# power.net
KiCad netlist of a schematic drawn in Altium Designer
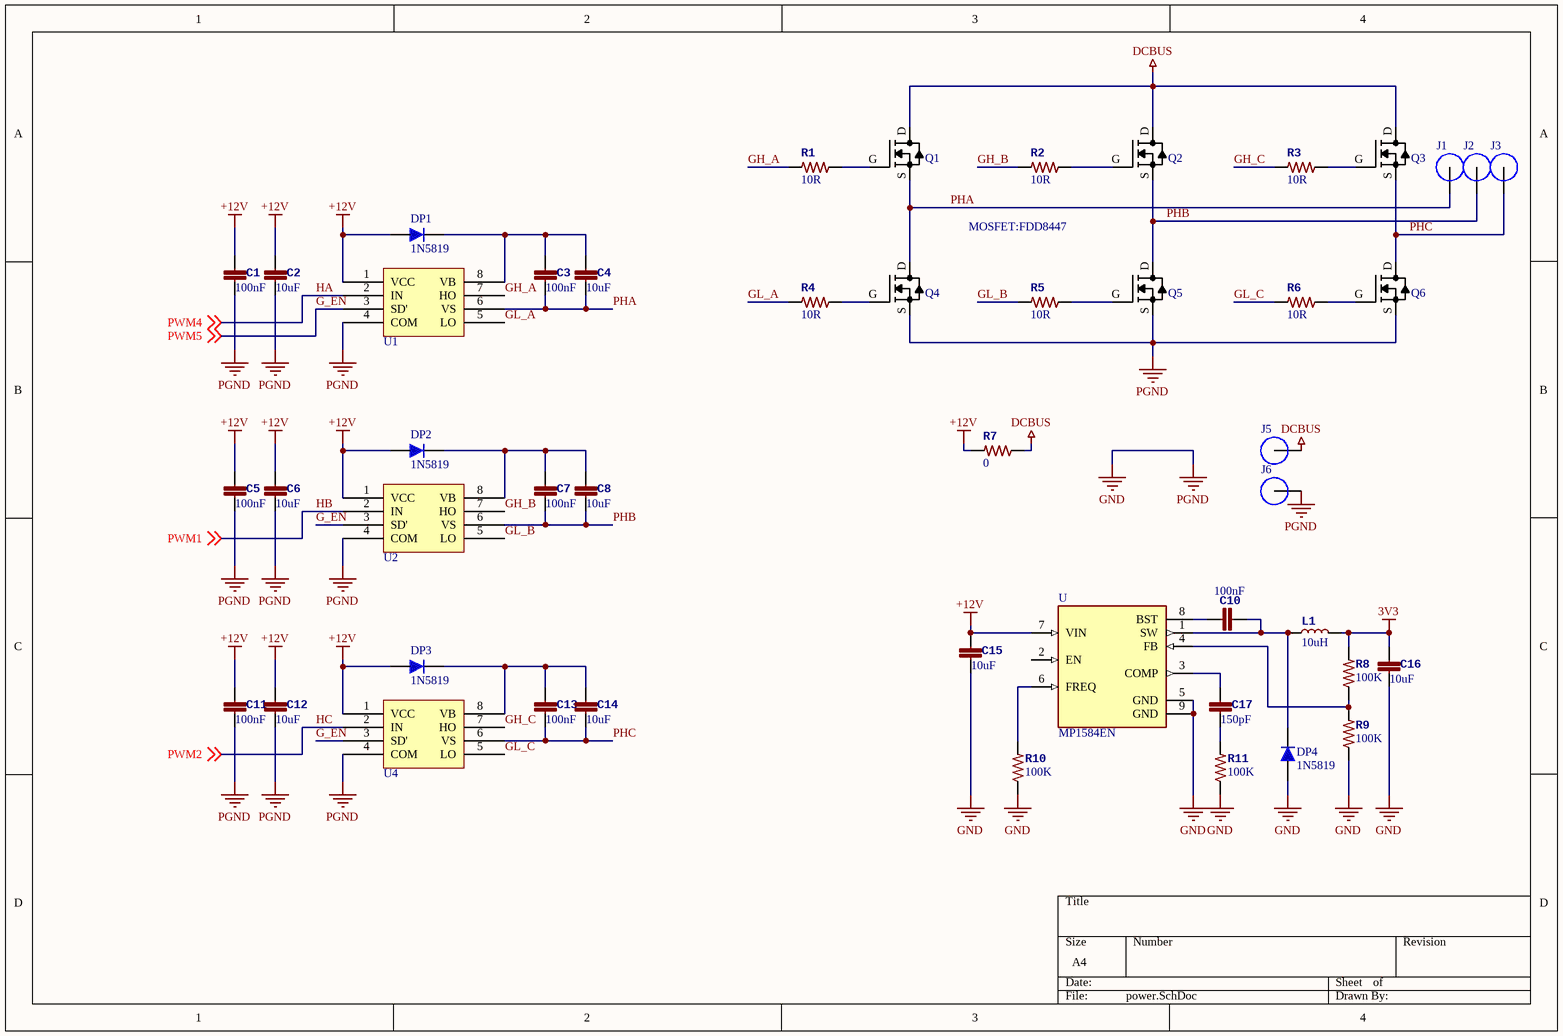
[diagram p0: power.SchDoc]

(export (version "E")
  (design (tool "Eeschema 10.0.6"))
  (components
    (comp (ref "C1")
      (value "100nF")
      (footprint "_1206")
      (fields (field (name "Comment") "Cap"))
      (libsource (lib "") (part "Cap_1_1"))
    )
    (comp (ref "C2")
      (value "10uF")
      (footprint "_1206")
      (fields (field (name "Comment") "Cap"))
      (libsource (lib "") (part "Cap_1_1"))
    )
    (comp (ref "C3")
      (value "100nF")
      (footprint "_1206")
      (fields (field (name "Comment") "Cap"))
      (libsource (lib "") (part "Cap_1_1"))
    )
    (comp (ref "C4")
      (value "10uF")
      (footprint "_1206")
      (fields (field (name "Comment") "Cap"))
      (libsource (lib "") (part "Cap_1_1"))
    )
    (comp (ref "C5")
      (value "100nF")
      (footprint "_1206")
      (fields (field (name "Comment") "Cap"))
      (libsource (lib "") (part "Cap_1_1"))
    )
    (comp (ref "C6")
      (value "10uF")
      (footprint "_1206")
      (fields (field (name "Comment") "Cap"))
      (libsource (lib "") (part "Cap_1_1"))
    )
    (comp (ref "C7")
      (value "100nF")
      (footprint "_1206")
      (fields (field (name "Comment") "Cap"))
      (libsource (lib "") (part "Cap_1_1"))
    )
    (comp (ref "C8")
      (value "10uF")
      (footprint "_1206")
      (fields (field (name "Comment") "Cap"))
      (libsource (lib "") (part "Cap_1_1"))
    )
    (comp (ref "C10")
      (value "100nF")
      (footprint "_0805")
      (fields (field (name "Comment") "Cap"))
      (libsource (lib "Passives_Integrated_Library") (part "Cap_1"))
    )
    (comp (ref "C11")
      (value "100nF")
      (footprint "_1206")
      (fields (field (name "Comment") "Cap"))
      (libsource (lib "") (part "Cap_1_1"))
    )
    (comp (ref "C12")
      (value "10uF")
      (footprint "_1206")
      (fields (field (name "Comment") "Cap"))
      (libsource (lib "") (part "Cap_1_1"))
    )
    (comp (ref "C13")
      (value "100nF")
      (footprint "_1206")
      (fields (field (name "Comment") "Cap"))
      (libsource (lib "") (part "Cap_1_1"))
    )
    (comp (ref "C14")
      (value "10uF")
      (footprint "_1206")
      (fields (field (name "Comment") "Cap"))
      (libsource (lib "") (part "Cap_1_1"))
    )
    (comp (ref "C15")
      (value "10uF")
      (footprint "_1206")
      (fields (field (name "Comment") "Cap"))
      (libsource (lib "") (part "Cap_1_1"))
    )
    (comp (ref "C16")
      (value "10uF")
      (footprint "_1206")
      (fields (field (name "Comment") "Cap"))
      (libsource (lib "") (part "Cap_1_1"))
    )
    (comp (ref "C17")
      (value "150pF")
      (footprint "_0805")
      (fields (field (name "Comment") "Cap"))
      (libsource (lib "") (part "Cap_1_1"))
    )
    (comp (ref "DP1")
      (value "1N5819")
      (footprint "430X270D")
      (description "Schottkey Rectifiers")
      (fields (field (name "DESIGNER") "Abbas Basereh"))
      (libsource (lib "Diodes_Integrated_Library") (part "1N5819"))
    )
    (comp (ref "DP2")
      (value "1N5819")
      (footprint "430X270D")
      (description "Schottkey Rectifiers")
      (fields (field (name "DESIGNER") "Abbas Basereh"))
      (libsource (lib "Diodes_Integrated_Library") (part "1N5819"))
    )
    (comp (ref "DP3")
      (value "1N5819")
      (footprint "430X270D")
      (description "Schottkey Rectifiers")
      (fields (field (name "DESIGNER") "Abbas Basereh"))
      (libsource (lib "Diodes_Integrated_Library") (part "1N5819"))
    )
    (comp (ref "DP4")
      (value "1N5819")
      (footprint "430X270D")
      (description "Schottkey Rectifiers")
      (fields (field (name "DESIGNER") "Abbas Basereh"))
      (libsource (lib "Diodes_Integrated_Library") (part "1N5819"))
    )
    (comp (ref "J1")
      (value "~")
      (footprint "M3 Spade Hole")
      (description "M3 Spade Terminal")
      (libsource (lib "CustomComponents") (part "M3 Spade Terminal"))
    )
    (comp (ref "J2")
      (value "~")
      (footprint "M3 Spade Hole")
      (description "M3 Spade Terminal")
      (libsource (lib "CustomComponents") (part "M3 Spade Terminal"))
    )
    (comp (ref "J3")
      (value "~")
      (footprint "M3 Spade Hole")
      (description "M3 Spade Terminal")
      (libsource (lib "CustomComponents") (part "M3 Spade Terminal"))
    )
    (comp (ref "J5")
      (value "~")
      (footprint "M3 Spade Hole")
      (description "M3 Spade Terminal")
      (libsource (lib "CustomComponents") (part "M3 Spade Terminal"))
    )
    (comp (ref "J6")
      (value "~")
      (footprint "M3 Spade Hole")
      (description "M3 Spade Terminal")
      (libsource (lib "CustomComponents") (part "M3 Spade Terminal"))
    )
    (comp (ref "L1")
      (value "10uH")
      (footprint "_INDUCTOR-SMD-6.0mm")
      (fields (field (name "Comment") "Inductor"))
      (libsource (lib "Passives_Integrated_Library") (part "Inductor"))
    )
    (comp (ref "Q1")
      (value "FILL_FOOTPRINT")
      (footprint "TO229P994X240-3N")
      (description "MOSFET N-CH 30V 13A SO8FL")
      (fields
        (field (name "MANUFACTURER") "ON Semiconductor")
        (field (name "MANUFACTURER PART NUMBER") "NTMFS4935NT1G")
      )
      (libsource (lib "Integrated_Library1") (part "NTMFS4935NT1G"))
    )
    (comp (ref "Q2")
      (value "FILL_FOOTPRINT")
      (footprint "TO229P994X240-3N")
      (description "MOSFET N-CH 30V 13A SO8FL")
      (fields
        (field (name "MANUFACTURER") "ON Semiconductor")
        (field (name "MANUFACTURER PART NUMBER") "NTMFS4935NT1G")
      )
      (libsource (lib "Integrated_Library1") (part "NTMFS4935NT1G"))
    )
    (comp (ref "Q3")
      (value "FILL_FOOTPRINT")
      (footprint "TO229P994X240-3N")
      (description "MOSFET N-CH 30V 13A SO8FL")
      (fields
        (field (name "MANUFACTURER") "ON Semiconductor")
        (field (name "MANUFACTURER PART NUMBER") "NTMFS4935NT1G")
      )
      (libsource (lib "Integrated_Library1") (part "NTMFS4935NT1G"))
    )
    (comp (ref "Q4")
      (value "FILL_FOOTPRINT")
      (footprint "TO229P994X240-3N")
      (description "MOSFET N-CH 30V 13A SO8FL")
      (fields
        (field (name "MANUFACTURER") "ON Semiconductor")
        (field (name "MANUFACTURER PART NUMBER") "NTMFS4935NT1G")
      )
      (libsource (lib "Integrated_Library1") (part "NTMFS4935NT1G"))
    )
    (comp (ref "Q5")
      (value "FILL_FOOTPRINT")
      (footprint "TO229P994X240-3N")
      (description "MOSFET N-CH 30V 13A SO8FL")
      (fields
        (field (name "MANUFACTURER") "ON Semiconductor")
        (field (name "MANUFACTURER PART NUMBER") "NTMFS4935NT1G")
      )
      (libsource (lib "Integrated_Library1") (part "NTMFS4935NT1G"))
    )
    (comp (ref "Q6")
      (value "FILL_FOOTPRINT")
      (footprint "TO229P994X240-3N")
      (description "MOSFET N-CH 30V 13A SO8FL")
      (fields
        (field (name "MANUFACTURER") "ON Semiconductor")
        (field (name "MANUFACTURER PART NUMBER") "NTMFS4935NT1G")
      )
      (libsource (lib "Integrated_Library1") (part "NTMFS4935NT1G"))
    )
    (comp (ref "R1")
      (value "10R")
      (footprint "_0805")
      (fields (field (name "Comment") "Resistor"))
      (libsource (lib "Passives_Integrated_Library") (part "Resistor"))
    )
    (comp (ref "R2")
      (value "10R")
      (footprint "_0805")
      (fields (field (name "Comment") "Resistor"))
      (libsource (lib "Passives_Integrated_Library") (part "Resistor"))
    )
    (comp (ref "R3")
      (value "10R")
      (footprint "_0805")
      (fields (field (name "Comment") "Resistor"))
      (libsource (lib "Passives_Integrated_Library") (part "Resistor"))
    )
    (comp (ref "R4")
      (value "10R")
      (footprint "_0805")
      (fields (field (name "Comment") "Resistor"))
      (libsource (lib "Passives_Integrated_Library") (part "Resistor"))
    )
    (comp (ref "R5")
      (value "10R")
      (footprint "_0805")
      (fields (field (name "Comment") "Resistor"))
      (libsource (lib "Passives_Integrated_Library") (part "Resistor"))
    )
    (comp (ref "R6")
      (value "10R")
      (footprint "_0805")
      (fields (field (name "Comment") "Resistor"))
      (libsource (lib "Passives_Integrated_Library") (part "Resistor"))
    )
    (comp (ref "R7")
      (value "0")
      (footprint "_1206")
      (fields (field (name "Comment") "Resistor"))
      (libsource (lib "Passives_Integrated_Library") (part "Resistor"))
    )
    (comp (ref "R8")
      (value "100K")
      (footprint "_0805")
      (fields (field (name "Comment") "Resistor"))
      (libsource (lib "Passives_Integrated_Library") (part "Resistor"))
    )
    (comp (ref "R9")
      (value "100K")
      (footprint "_0805")
      (fields (field (name "Comment") "Resistor"))
      (libsource (lib "Passives_Integrated_Library") (part "Resistor"))
    )
    (comp (ref "R10")
      (value "100K")
      (footprint "_0805")
      (fields (field (name "Comment") "Resistor"))
      (libsource (lib "Passives_Integrated_Library") (part "Resistor"))
    )
    (comp (ref "R11")
      (value "100K")
      (footprint "_0805")
      (fields (field (name "Comment") "Resistor"))
      (libsource (lib "Passives_Integrated_Library") (part "Resistor"))
    )
    (comp (ref "U")
      (value "MP1584EN")
      (footprint "SOIC127P600X170-9N")
      (fields (field (name "MF") "Monolithic Power"))
      (libsource (lib "MP1584EN") (part "MP1584EN"))
    )
    (comp (ref "U1")
      (value "IR2104")
      (footprint "_SO08")
      (libsource (lib "Power_Electronics_Integrated_Library") (part "IR2104"))
    )
    (comp (ref "U2")
      (value "IR2104")
      (footprint "_SO08")
      (libsource (lib "Power_Electronics_Integrated_Library") (part "IR2104"))
    )
    (comp (ref "U4")
      (value "IR2104")
      (footprint "_SO08")
      (libsource (lib "Power_Electronics_Integrated_Library") (part "IR2104"))
    )
  )
  (nets
    (net (code "1") (name "+12V") (class "Default")
      (node (ref "C1") (pin "1") (pinfunction "1_1") (pintype "passive"))
      (node (ref "C11") (pin "1") (pinfunction "1_1") (pintype "passive"))
      (node (ref "C12") (pin "1") (pinfunction "1_1") (pintype "passive"))
      (node (ref "C15") (pin "1") (pinfunction "1_1") (pintype "passive"))
      (node (ref "C2") (pin "1") (pinfunction "1_1") (pintype "passive"))
      (node (ref "C5") (pin "1") (pinfunction "1_1") (pintype "passive"))
      (node (ref "C6") (pin "1") (pinfunction "1_1") (pintype "passive"))
      (node (ref "DP1") (pin "1") (pintype "passive"))
      (node (ref "DP2") (pin "1") (pintype "passive"))
      (node (ref "DP3") (pin "1") (pintype "passive"))
      (node (ref "R7") (pin "2") (pinfunction "2_2") (pintype "passive"))
      (node (ref "U") (pin "7") (pinfunction "VIN_7") (pintype "input"))
      (node (ref "U1") (pin "1") (pinfunction "VCC_1") (pintype "passive"))
      (node (ref "U2") (pin "1") (pinfunction "VCC_1") (pintype "passive"))
      (node (ref "U4") (pin "1") (pinfunction "VCC_1") (pintype "passive"))
    )
    (net (code "2") (name "/GH_A") (class "Default")
      (node (ref "R1") (pin "2") (pinfunction "2_2") (pintype "passive"))
      (node (ref "U1") (pin "7") (pinfunction "HO_7") (pintype "passive"))
    )
    (net (code "3") (name "/GH_B") (class "Default")
      (node (ref "R2") (pin "2") (pinfunction "2_2") (pintype "passive"))
      (node (ref "U2") (pin "7") (pinfunction "HO_7") (pintype "passive"))
    )
    (net (code "4") (name "/GH_C") (class "Default")
      (node (ref "R3") (pin "2") (pinfunction "2_2") (pintype "passive"))
      (node (ref "U4") (pin "7") (pinfunction "HO_7") (pintype "passive"))
    )
    (net (code "5") (name "/GL_A") (class "Default")
      (node (ref "R4") (pin "2") (pinfunction "2_2") (pintype "passive"))
      (node (ref "U1") (pin "5") (pinfunction "LO_5") (pintype "passive"))
    )
    (net (code "6") (name "/GL_B") (class "Default")
      (node (ref "R5") (pin "2") (pinfunction "2_2") (pintype "passive"))
      (node (ref "U2") (pin "5") (pinfunction "LO_5") (pintype "passive"))
    )
    (net (code "7") (name "/GL_C") (class "Default")
      (node (ref "R6") (pin "2") (pinfunction "2_2") (pintype "passive"))
      (node (ref "U4") (pin "5") (pinfunction "LO_5") (pintype "passive"))
    )
    (net (code "8") (name "/PHA") (class "Default")
      (node (ref "C3") (pin "2") (pinfunction "2_2") (pintype "passive"))
      (node (ref "C4") (pin "2") (pinfunction "2_2") (pintype "passive"))
      (node (ref "J1") (pin "1") (pinfunction "1_1") (pintype "passive"))
      (node (ref "Q1") (pin "S") (pinfunction "S_S") (pintype "passive"))
      (node (ref "Q4") (pin "D") (pinfunction "D_D") (pintype "passive"))
      (node (ref "U1") (pin "6") (pinfunction "VS_6") (pintype "passive"))
    )
    (net (code "9") (name "/PHB") (class "Default")
      (node (ref "C7") (pin "2") (pinfunction "2_2") (pintype "passive"))
      (node (ref "C8") (pin "2") (pinfunction "2_2") (pintype "passive"))
      (node (ref "J2") (pin "1") (pinfunction "1_1") (pintype "passive"))
      (node (ref "Q2") (pin "S") (pinfunction "S_S") (pintype "passive"))
      (node (ref "Q5") (pin "D") (pinfunction "D_D") (pintype "passive"))
      (node (ref "U2") (pin "6") (pinfunction "VS_6") (pintype "passive"))
    )
    (net (code "10") (name "/PHC") (class "Default")
      (node (ref "C13") (pin "2") (pinfunction "2_2") (pintype "passive"))
      (node (ref "C14") (pin "2") (pinfunction "2_2") (pintype "passive"))
      (node (ref "J3") (pin "1") (pinfunction "1_1") (pintype "passive"))
      (node (ref "Q3") (pin "S") (pinfunction "S_S") (pintype "passive"))
      (node (ref "Q6") (pin "D") (pinfunction "D_D") (pintype "passive"))
      (node (ref "U4") (pin "6") (pinfunction "VS_6") (pintype "passive"))
    )
    (net (code "11") (name "3V3") (class "Default")
      (node (ref "C16") (pin "1") (pinfunction "1_1") (pintype "passive"))
      (node (ref "L1") (pin "2") (pinfunction "2_2") (pintype "passive"))
      (node (ref "R8") (pin "2") (pinfunction "2_2") (pintype "passive"))
    )
    (net (code "12") (name "DCBUS") (class "Default")
      (node (ref "J5") (pin "1") (pinfunction "1_1") (pintype "passive"))
      (node (ref "Q1") (pin "D") (pinfunction "D_D") (pintype "passive"))
      (node (ref "Q2") (pin "D") (pinfunction "D_D") (pintype "passive"))
      (node (ref "Q3") (pin "D") (pinfunction "D_D") (pintype "passive"))
      (node (ref "R7") (pin "1") (pinfunction "1_1") (pintype "passive"))
    )
    (net (code "13") (name "GND") (class "Default")
      (node (ref "C1") (pin "2") (pinfunction "2_2") (pintype "passive"))
      (node (ref "C11") (pin "2") (pinfunction "2_2") (pintype "passive"))
      (node (ref "C12") (pin "2") (pinfunction "2_2") (pintype "passive"))
      (node (ref "C15") (pin "2") (pinfunction "2_2") (pintype "passive"))
      (node (ref "C16") (pin "2") (pinfunction "2_2") (pintype "passive"))
      (node (ref "C2") (pin "2") (pinfunction "2_2") (pintype "passive"))
      (node (ref "C5") (pin "2") (pinfunction "2_2") (pintype "passive"))
      (node (ref "C6") (pin "2") (pinfunction "2_2") (pintype "passive"))
      (node (ref "DP4") (pin "1") (pintype "passive"))
      (node (ref "J6") (pin "1") (pinfunction "1_1") (pintype "passive"))
      (node (ref "Q4") (pin "S") (pinfunction "S_S") (pintype "passive"))
      (node (ref "Q5") (pin "S") (pinfunction "S_S") (pintype "passive"))
      (node (ref "Q6") (pin "S") (pinfunction "S_S") (pintype "passive"))
      (node (ref "R10") (pin "1") (pinfunction "1_1") (pintype "passive"))
      (node (ref "R11") (pin "1") (pinfunction "1_1") (pintype "passive"))
      (node (ref "R9") (pin "1") (pinfunction "1_1") (pintype "passive"))
      (node (ref "U") (pin "5") (pinfunction "GND_5") (pintype "power_in"))
      (node (ref "U") (pin "9") (pinfunction "GND_9") (pintype "power_in"))
      (node (ref "U1") (pin "4") (pinfunction "COM_4") (pintype "passive"))
      (node (ref "U2") (pin "4") (pinfunction "COM_4") (pintype "passive"))
      (node (ref "U4") (pin "4") (pinfunction "COM_4") (pintype "passive"))
    )
    (net (code "14") (name "Net-(C17-Pad2)") (class "Default")
      (node (ref "C17") (pin "2") (pinfunction "2_2") (pintype "passive"))
      (node (ref "R11") (pin "2") (pinfunction "2_2") (pintype "passive"))
    )
    (net (code "15") (name "Net-(Q1-PadG)") (class "Default")
      (node (ref "Q1") (pin "G") (pinfunction "G_G") (pintype "passive"))
      (node (ref "R1") (pin "1") (pinfunction "1_1") (pintype "passive"))
    )
    (net (code "16") (name "Net-(Q2-PadG)") (class "Default")
      (node (ref "Q2") (pin "G") (pinfunction "G_G") (pintype "passive"))
      (node (ref "R2") (pin "1") (pinfunction "1_1") (pintype "passive"))
    )
    (net (code "17") (name "Net-(Q3-PadG)") (class "Default")
      (node (ref "Q3") (pin "G") (pinfunction "G_G") (pintype "passive"))
      (node (ref "R3") (pin "1") (pinfunction "1_1") (pintype "passive"))
    )
    (net (code "18") (name "Net-(Q4-PadG)") (class "Default")
      (node (ref "Q4") (pin "G") (pinfunction "G_G") (pintype "passive"))
      (node (ref "R4") (pin "1") (pinfunction "1_1") (pintype "passive"))
    )
    (net (code "19") (name "Net-(Q5-PadG)") (class "Default")
      (node (ref "Q5") (pin "G") (pinfunction "G_G") (pintype "passive"))
      (node (ref "R5") (pin "1") (pinfunction "1_1") (pintype "passive"))
    )
    (net (code "20") (name "Net-(Q6-PadG)") (class "Default")
      (node (ref "Q6") (pin "G") (pinfunction "G_G") (pintype "passive"))
      (node (ref "R6") (pin "1") (pinfunction "1_1") (pintype "passive"))
    )
    (net (code "21") (name "Net-(U-BST)") (class "Default")
      (node (ref "C10") (pin "1") (pinfunction "1_1") (pintype "passive"))
      (node (ref "U") (pin "8") (pinfunction "BST_8") (pintype "passive"))
    )
    (net (code "22") (name "Net-(U-COMP)") (class "Default")
      (node (ref "C17") (pin "1") (pinfunction "1_1") (pintype "passive"))
      (node (ref "U") (pin "3") (pinfunction "COMP_3") (pintype "output"))
    )
    (net (code "23") (name "Net-(U-FB)") (class "Default")
      (node (ref "R8") (pin "1") (pinfunction "1_1") (pintype "passive"))
      (node (ref "R9") (pin "2") (pinfunction "2_2") (pintype "passive"))
      (node (ref "U") (pin "4") (pinfunction "FB_4") (pintype "input"))
    )
    (net (code "24") (name "Net-(U-FREQ)") (class "Default")
      (node (ref "R10") (pin "2") (pinfunction "2_2") (pintype "passive"))
      (node (ref "U") (pin "6") (pinfunction "FREQ_6") (pintype "input"))
    )
    (net (code "25") (name "Net-(U-SW)") (class "Default")
      (node (ref "C10") (pin "2") (pinfunction "2_2") (pintype "passive"))
      (node (ref "DP4") (pin "2") (pintype "passive"))
      (node (ref "L1") (pin "1") (pinfunction "1_1") (pintype "passive"))
      (node (ref "U") (pin "1") (pinfunction "SW_1") (pintype "output"))
    )
    (net (code "26") (name "Net-(U1-VB)") (class "Default")
      (node (ref "C3") (pin "1") (pinfunction "1_1") (pintype "passive"))
      (node (ref "C4") (pin "1") (pinfunction "1_1") (pintype "passive"))
      (node (ref "DP1") (pin "2") (pintype "passive"))
      (node (ref "U1") (pin "8") (pinfunction "VB_8") (pintype "passive"))
    )
    (net (code "27") (name "Net-(U2-VB)") (class "Default")
      (node (ref "C7") (pin "1") (pinfunction "1_1") (pintype "passive"))
      (node (ref "C8") (pin "1") (pinfunction "1_1") (pintype "passive"))
      (node (ref "DP2") (pin "2") (pintype "passive"))
      (node (ref "U2") (pin "8") (pinfunction "VB_8") (pintype "passive"))
    )
    (net (code "28") (name "Net-(U4-VB)") (class "Default")
      (node (ref "C13") (pin "1") (pinfunction "1_1") (pintype "passive"))
      (node (ref "C14") (pin "1") (pinfunction "1_1") (pintype "passive"))
      (node (ref "DP3") (pin "2") (pintype "passive"))
      (node (ref "U4") (pin "8") (pinfunction "VB_8") (pintype "passive"))
    )
    (net (code "29") (name "PWM1") (class "Default")
      (node (ref "U2") (pin "2") (pinfunction "IN_2") (pintype "passive"))
    )
    (net (code "30") (name "PWM2") (class "Default")
      (node (ref "U4") (pin "2") (pinfunction "IN_2") (pintype "passive"))
    )
    (net (code "31") (name "PWM4") (class "Default")
      (node (ref "U1") (pin "2") (pinfunction "IN_2") (pintype "passive"))
    )
    (net (code "32") (name "PWM5") (class "Default")
      (node (ref "U1") (pin "3") (pinfunction "SD'_3") (pintype "passive"))
      (node (ref "U2") (pin "3") (pinfunction "SD'_3") (pintype "passive"))
      (node (ref "U4") (pin "3") (pinfunction "SD'_3") (pintype "passive"))
    )
    (net (code "33") (name "unconnected-(U-EN-Pad2)") (class "Default")
      (node (ref "U") (pin "2") (pinfunction "EN_2") (pintype "input"))
    )
  )
)
